# ZoomFloppy_v1_0.net
KiCad netlist of a schematic drawn in EAGLE
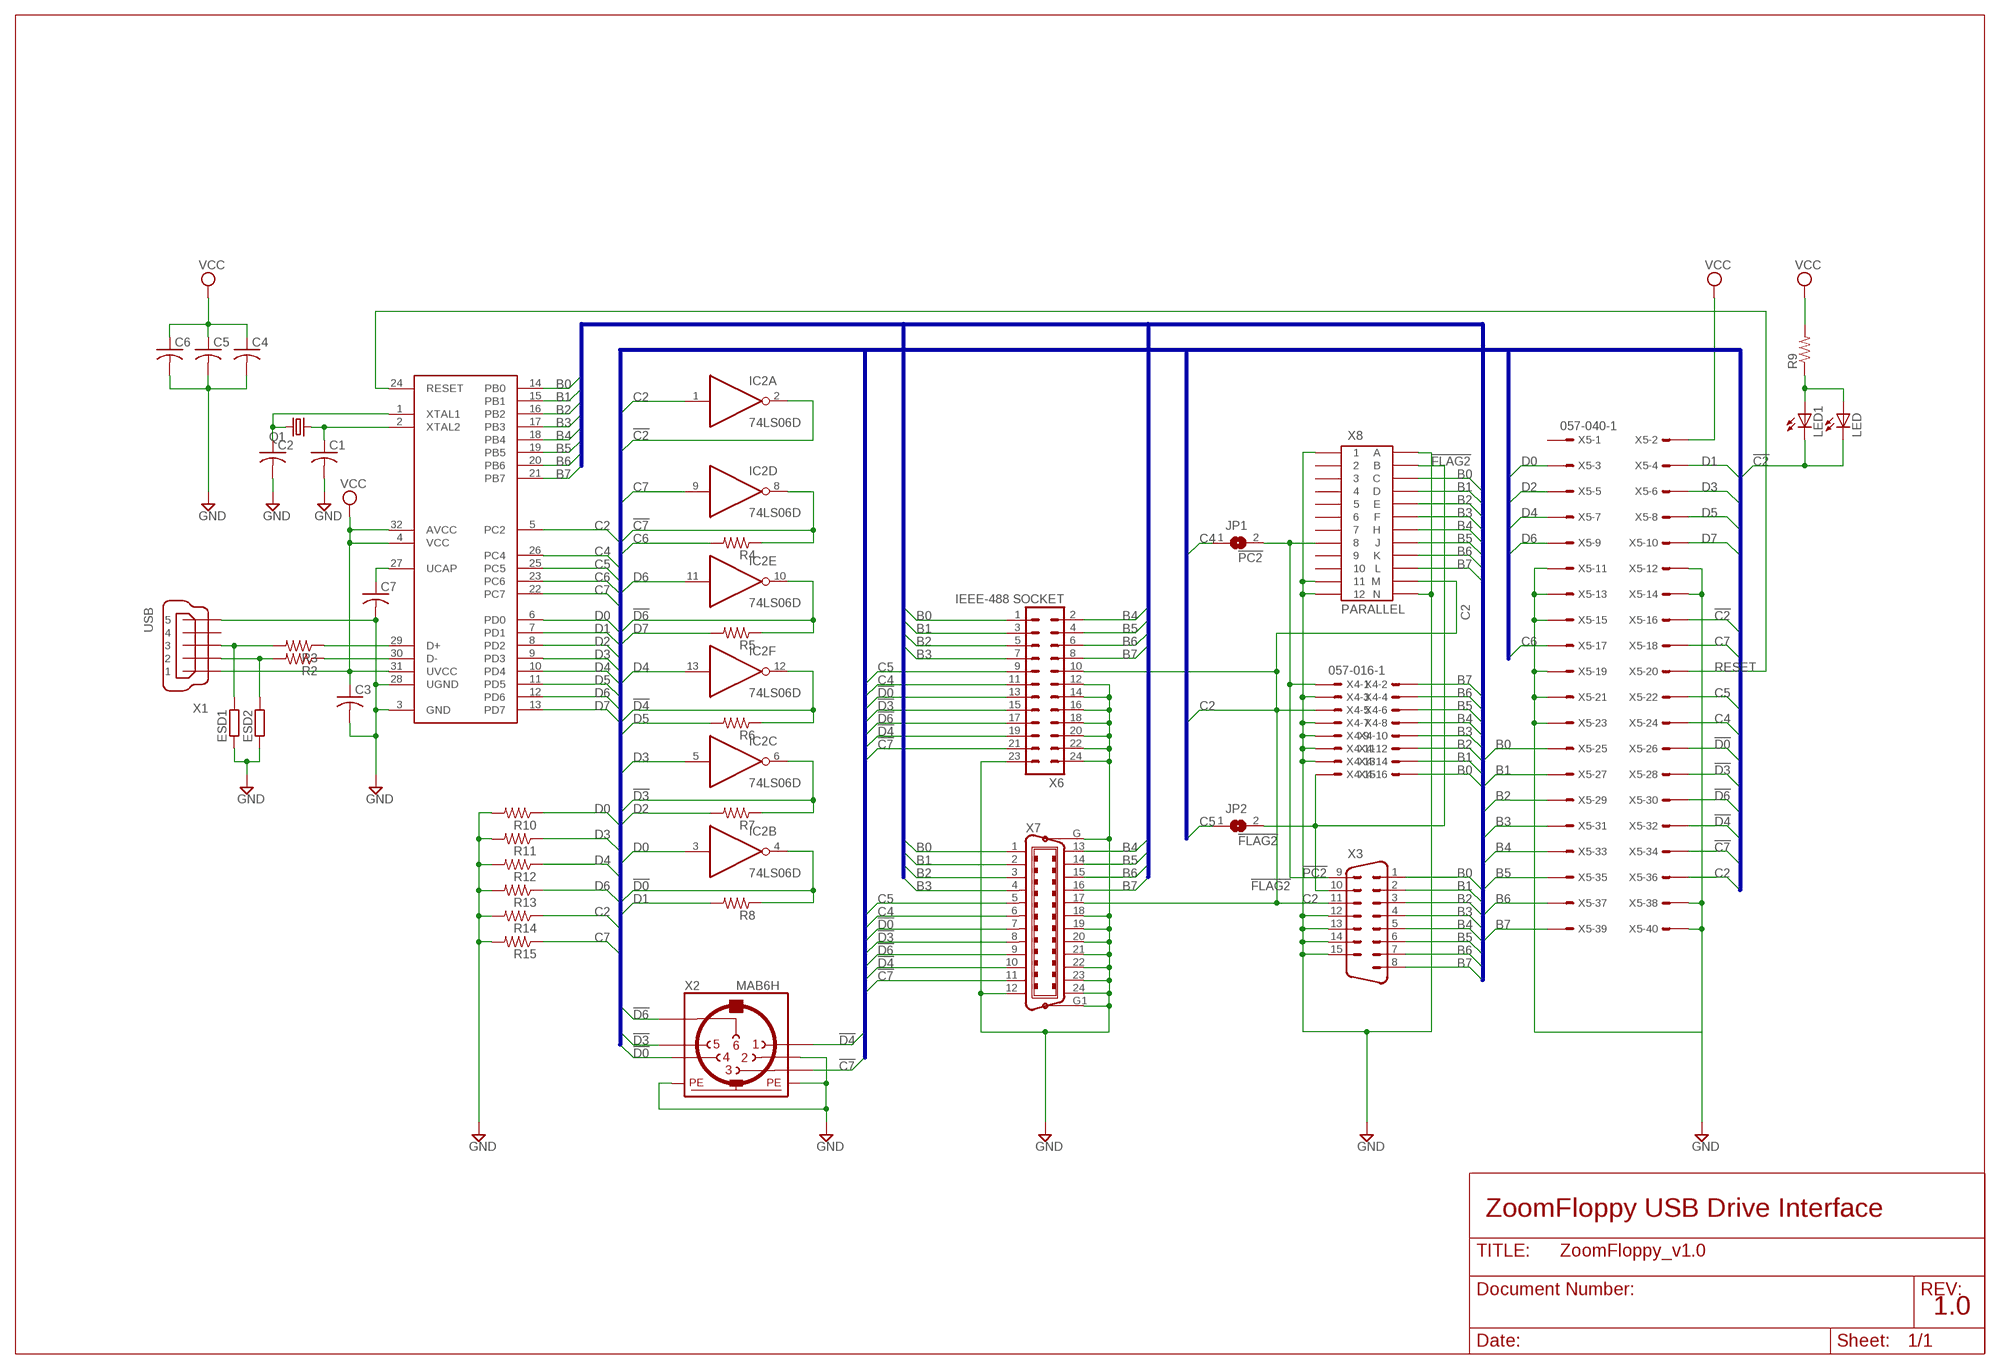
[diagram p0: schematic, sheet 1]

(export (version "E")
  (design (tool "Eeschema 10.0.6"))
  (components
    (comp (ref "C1")
      (value "C-USC0402")
      (footprint "eagle-import:C0402")
      (libsource (lib "eagle-import") (part "C-USC0402"))
    )
    (comp (ref "C2")
      (value "C-USC0402")
      (footprint "eagle-import:C0402")
      (libsource (lib "eagle-import") (part "C-USC0402"))
    )
    (comp (ref "C3")
      (value "C-USC0402")
      (footprint "eagle-import:C0402")
      (libsource (lib "eagle-import") (part "C-USC0402"))
    )
    (comp (ref "C4")
      (value "C-USC0402")
      (footprint "eagle-import:C0402")
      (libsource (lib "eagle-import") (part "C-USC0402"))
    )
    (comp (ref "C5")
      (value "C-USC0402")
      (footprint "eagle-import:C0402")
      (libsource (lib "eagle-import") (part "C-USC0402"))
    )
    (comp (ref "C6")
      (value "C-USC0402")
      (footprint "eagle-import:C0402")
      (libsource (lib "eagle-import") (part "C-USC0402"))
    )
    (comp (ref "C7")
      (value "C-USC0402")
      (footprint "eagle-import:C0402")
      (libsource (lib "eagle-import") (part "C-USC0402"))
    )
    (comp (ref "ESD1")
      (value "R-EU_R0603")
      (footprint "eagle-import:R0603")
      (libsource (lib "eagle-import") (part "R-EU_R0603"))
    )
    (comp (ref "ESD2")
      (value "R-EU_R0603")
      (footprint "eagle-import:R0603")
      (libsource (lib "eagle-import") (part "R-EU_R0603"))
    )
    (comp (ref "IC1")
      (value "ATMEGA32U2")
      (footprint "eagle-import:VQFP32")
      (libsource (lib "eagle-import") (part "AT90USB162"))
    )
    (comp (ref "IC2")
      (value "74LS06D")
      (footprint "eagle-import:SO14")
      (libsource (lib "eagle-import") (part "7406DLS"))
    )
    (comp (ref "JP1") (value "SJ") (footprint "eagle-import:SJ") (libsource (lib "eagle-import") (part "SJ")))
    (comp (ref "JP2") (value "SJ") (footprint "eagle-import:SJ") (libsource (lib "eagle-import") (part "SJ")))
    (comp (ref "LED")
      (value "LED3MM")
      (footprint "eagle-import:LED3MM")
      (libsource (lib "eagle-import") (part "LED3MM"))
    )
    (comp (ref "LED1")
      (value "LEDCHIP-LED0805")
      (footprint "eagle-import:CHIP-LED0805")
      (libsource (lib "eagle-import") (part "LEDCHIP-LED0805"))
    )
    (comp (ref "Q1")
      (value "CRYSTALHC49UP")
      (footprint "eagle-import:HC49UP")
      (libsource (lib "eagle-import") (part "CRYSTALHC49UP"))
    )
    (comp (ref "R2")
      (value "R-US_R0402")
      (footprint "eagle-import:R0402")
      (libsource (lib "eagle-import") (part "R-US_R0402"))
    )
    (comp (ref "R3")
      (value "R-US_R0402")
      (footprint "eagle-import:R0402")
      (libsource (lib "eagle-import") (part "R-US_R0402"))
    )
    (comp (ref "R4")
      (value "R-US_R0402")
      (footprint "eagle-import:R0402")
      (libsource (lib "eagle-import") (part "R-US_R0402"))
    )
    (comp (ref "R5")
      (value "R-US_R0402")
      (footprint "eagle-import:R0402")
      (libsource (lib "eagle-import") (part "R-US_R0402"))
    )
    (comp (ref "R6")
      (value "R-US_R0402")
      (footprint "eagle-import:R0402")
      (libsource (lib "eagle-import") (part "R-US_R0402"))
    )
    (comp (ref "R7")
      (value "R-US_R0402")
      (footprint "eagle-import:R0402")
      (libsource (lib "eagle-import") (part "R-US_R0402"))
    )
    (comp (ref "R8")
      (value "R-US_R0402")
      (footprint "eagle-import:R0402")
      (libsource (lib "eagle-import") (part "R-US_R0402"))
    )
    (comp (ref "R9")
      (value "R-US_R0402")
      (footprint "eagle-import:R0402")
      (libsource (lib "eagle-import") (part "R-US_R0402"))
    )
    (comp (ref "R10")
      (value "R-US_R0402")
      (footprint "eagle-import:R0402")
      (libsource (lib "eagle-import") (part "R-US_R0402"))
    )
    (comp (ref "R11")
      (value "R-US_R0402")
      (footprint "eagle-import:R0402")
      (libsource (lib "eagle-import") (part "R-US_R0402"))
    )
    (comp (ref "R12")
      (value "R-US_R0402")
      (footprint "eagle-import:R0402")
      (libsource (lib "eagle-import") (part "R-US_R0402"))
    )
    (comp (ref "R13")
      (value "R-US_R0402")
      (footprint "eagle-import:R0402")
      (libsource (lib "eagle-import") (part "R-US_R0402"))
    )
    (comp (ref "R14")
      (value "R-US_R0402")
      (footprint "eagle-import:R0402")
      (libsource (lib "eagle-import") (part "R-US_R0402"))
    )
    (comp (ref "R15")
      (value "R-US_R0402")
      (footprint "eagle-import:R0402")
      (libsource (lib "eagle-import") (part "R-US_R0402"))
    )
    (comp (ref "X1")
      (value "USB")
      (footprint "eagle-import:UX60-MB-5ST")
      (libsource (lib "eagle-import") (part "MINI-USB-UX60-MB-5ST"))
    )
    (comp (ref "X2")
      (value "MAB6H")
      (footprint "eagle-import:MAB6H")
      (libsource (lib "eagle-import") (part "MAB6H"))
    )
    (comp (ref "X3")
      (value "M15-182")
      (footprint "eagle-import:182-015-MALE")
      (libsource (lib "eagle-import") (part "M15-182"))
    )
    (comp (ref "X4")
      (value "057-016-1")
      (footprint "eagle-import:057-016-1")
      (libsource (lib "eagle-import") (part "057-016-1"))
    )
    (comp (ref "X5")
      (value "057-040-1")
      (footprint "eagle-import:057-040-1")
      (libsource (lib "eagle-import") (part "057-040-1"))
    )
    (comp (ref "X6")
      (value "IEEE-488 SOCKET")
      (footprint "eagle-import:MA12-2")
      (libsource (lib "eagle-import") (part "MA12-2"))
    )
    (comp (ref "X7")
      (value "C24HP")
      (footprint "eagle-import:24HP")
      (libsource (lib "eagle-import") (part "C24HP"))
    )
    (comp (ref "X8")
      (value "PARALLEL")
      (footprint "eagle-import:MA-24")
      (libsource (lib "eagle-import") (part "MA-24"))
    )
  )
  (nets
    (net (code "1") (name "/B0") (class "Default")
      (node (ref "IC1") (pin "14") (pinfunction "PB0_14") (pintype "bidirectional"))
      (node (ref "X3") (pin "1") (pinfunction "1_1") (pintype "passive"))
      (node (ref "X4") (pin "16") (pinfunction "S_16") (pintype "passive"))
      (node (ref "X5") (pin "25") (pinfunction "S_25") (pintype "passive"))
      (node (ref "X6") (pin "1") (pinfunction "1_1") (pintype "passive"))
      (node (ref "X7") (pin "1") (pinfunction "1_1") (pintype "passive"))
      (node (ref "X8") (pin "C") (pinfunction "C_C") (pintype "passive"))
    )
    (net (code "2") (name "/B1") (class "Default")
      (node (ref "IC1") (pin "15") (pinfunction "PB1_15") (pintype "bidirectional"))
      (node (ref "X3") (pin "2") (pinfunction "2_2") (pintype "passive"))
      (node (ref "X4") (pin "14") (pinfunction "S_14") (pintype "passive"))
      (node (ref "X5") (pin "27") (pinfunction "S_27") (pintype "passive"))
      (node (ref "X6") (pin "3") (pinfunction "3_3") (pintype "passive"))
      (node (ref "X7") (pin "2") (pinfunction "2_2") (pintype "passive"))
      (node (ref "X8") (pin "D") (pinfunction "D_D") (pintype "passive"))
    )
    (net (code "3") (name "/B2") (class "Default")
      (node (ref "IC1") (pin "16") (pinfunction "PB2_16") (pintype "bidirectional"))
      (node (ref "X3") (pin "3") (pinfunction "3_3") (pintype "passive"))
      (node (ref "X4") (pin "12") (pinfunction "S_12") (pintype "passive"))
      (node (ref "X5") (pin "29") (pinfunction "S_29") (pintype "passive"))
      (node (ref "X6") (pin "5") (pinfunction "5_5") (pintype "passive"))
      (node (ref "X7") (pin "3") (pinfunction "3_3") (pintype "passive"))
      (node (ref "X8") (pin "E") (pinfunction "E_E") (pintype "passive"))
    )
    (net (code "4") (name "/B3") (class "Default")
      (node (ref "IC1") (pin "17") (pinfunction "PB3_17") (pintype "bidirectional"))
      (node (ref "X3") (pin "4") (pinfunction "4_4") (pintype "passive"))
      (node (ref "X4") (pin "10") (pinfunction "S_10") (pintype "passive"))
      (node (ref "X5") (pin "31") (pinfunction "S_31") (pintype "passive"))
      (node (ref "X6") (pin "7") (pinfunction "7_7") (pintype "passive"))
      (node (ref "X7") (pin "4") (pinfunction "4_4") (pintype "passive"))
      (node (ref "X8") (pin "F") (pinfunction "F_F") (pintype "passive"))
    )
    (net (code "5") (name "/B4") (class "Default")
      (node (ref "IC1") (pin "18") (pinfunction "PB4_18") (pintype "bidirectional"))
      (node (ref "X3") (pin "5") (pinfunction "5_5") (pintype "passive"))
      (node (ref "X4") (pin "8") (pinfunction "S_8") (pintype "passive"))
      (node (ref "X5") (pin "33") (pinfunction "S_33") (pintype "passive"))
      (node (ref "X6") (pin "2") (pinfunction "2_2") (pintype "passive"))
      (node (ref "X7") (pin "13") (pinfunction "13_13") (pintype "passive"))
      (node (ref "X8") (pin "H") (pinfunction "H_H") (pintype "passive"))
    )
    (net (code "6") (name "/B5") (class "Default")
      (node (ref "IC1") (pin "19") (pinfunction "PB5_19") (pintype "bidirectional"))
      (node (ref "X3") (pin "6") (pinfunction "6_6") (pintype "passive"))
      (node (ref "X4") (pin "6") (pinfunction "S_6") (pintype "passive"))
      (node (ref "X5") (pin "35") (pinfunction "S_35") (pintype "passive"))
      (node (ref "X6") (pin "4") (pinfunction "4_4") (pintype "passive"))
      (node (ref "X7") (pin "14") (pinfunction "14_14") (pintype "passive"))
      (node (ref "X8") (pin "J") (pinfunction "J_J") (pintype "passive"))
    )
    (net (code "7") (name "/B6") (class "Default")
      (node (ref "IC1") (pin "20") (pinfunction "PB6_20") (pintype "bidirectional"))
      (node (ref "X3") (pin "7") (pinfunction "7_7") (pintype "passive"))
      (node (ref "X4") (pin "4") (pinfunction "S_4") (pintype "passive"))
      (node (ref "X5") (pin "37") (pinfunction "S_37") (pintype "passive"))
      (node (ref "X6") (pin "6") (pinfunction "6_6") (pintype "passive"))
      (node (ref "X7") (pin "15") (pinfunction "15_15") (pintype "passive"))
      (node (ref "X8") (pin "K") (pinfunction "K_K") (pintype "passive"))
    )
    (net (code "8") (name "/B7") (class "Default")
      (node (ref "IC1") (pin "21") (pinfunction "PB7_21") (pintype "bidirectional"))
      (node (ref "X3") (pin "8") (pinfunction "8_8") (pintype "passive"))
      (node (ref "X4") (pin "2") (pinfunction "S_2") (pintype "passive"))
      (node (ref "X5") (pin "39") (pinfunction "S_39") (pintype "passive"))
      (node (ref "X6") (pin "8") (pinfunction "8_8") (pintype "passive"))
      (node (ref "X7") (pin "16") (pinfunction "16_16") (pintype "passive"))
      (node (ref "X8") (pin "L") (pinfunction "L_L") (pintype "passive"))
    )
    (net (code "9") (name "/C2") (class "Default")
      (node (ref "IC1") (pin "5") (pinfunction "PC2_5") (pintype "bidirectional"))
      (node (ref "IC2") (pin "1") (pinfunction "I_1") (pintype "input"))
      (node (ref "R14") (pin "1") (pinfunction "1_1") (pintype "passive"))
      (node (ref "X3") (pin "11") (pinfunction "11_11") (pintype "passive"))
      (node (ref "X4") (pin "5") (pinfunction "S_5") (pintype "passive"))
      (node (ref "X5") (pin "36") (pinfunction "S_36") (pintype "passive"))
      (node (ref "X6") (pin "10") (pinfunction "10_10") (pintype "passive"))
      (node (ref "X7") (pin "17") (pinfunction "17_17") (pintype "passive"))
      (node (ref "X8") (pin "M") (pinfunction "M_M") (pintype "passive"))
    )
    (net (code "10") (name "/C4") (class "Default")
      (node (ref "IC1") (pin "26") (pinfunction "PC4_26") (pintype "bidirectional"))
      (node (ref "JP1") (pin "1") (pinfunction "1_1") (pintype "passive"))
      (node (ref "X5") (pin "24") (pinfunction "S_24") (pintype "passive"))
      (node (ref "X6") (pin "11") (pinfunction "11_11") (pintype "passive"))
      (node (ref "X7") (pin "6") (pinfunction "6_6") (pintype "passive"))
    )
    (net (code "11") (name "/C5") (class "Default")
      (node (ref "IC1") (pin "25") (pinfunction "PC5_25") (pintype "bidirectional"))
      (node (ref "JP2") (pin "1") (pinfunction "1_1") (pintype "passive"))
      (node (ref "X5") (pin "22") (pinfunction "S_22") (pintype "passive"))
      (node (ref "X6") (pin "9") (pinfunction "9_9") (pintype "passive"))
      (node (ref "X7") (pin "5") (pinfunction "5_5") (pintype "passive"))
    )
    (net (code "12") (name "/C6") (class "Default")
      (node (ref "IC1") (pin "23") (pinfunction "PC6_23") (pintype "bidirectional"))
      (node (ref "R4") (pin "2") (pinfunction "2_2") (pintype "passive"))
      (node (ref "X5") (pin "17") (pinfunction "S_17") (pintype "passive"))
    )
    (net (code "13") (name "/C7") (class "Default")
      (node (ref "IC1") (pin "22") (pinfunction "PC7_22") (pintype "bidirectional"))
      (node (ref "IC2") (pin "9") (pinfunction "I_9") (pintype "input"))
      (node (ref "R15") (pin "1") (pinfunction "1_1") (pintype "passive"))
      (node (ref "X5") (pin "18") (pinfunction "S_18") (pintype "passive"))
    )
    (net (code "14") (name "/D0") (class "Default")
      (node (ref "IC1") (pin "6") (pinfunction "PD0_6") (pintype "bidirectional"))
      (node (ref "IC2") (pin "3") (pinfunction "I_3") (pintype "input"))
      (node (ref "R10") (pin "1") (pinfunction "1_1") (pintype "passive"))
      (node (ref "X5") (pin "3") (pinfunction "S_3") (pintype "passive"))
    )
    (net (code "15") (name "/D1") (class "Default")
      (node (ref "IC1") (pin "7") (pinfunction "PD1_7") (pintype "bidirectional"))
      (node (ref "R8") (pin "2") (pinfunction "2_2") (pintype "passive"))
      (node (ref "X5") (pin "4") (pinfunction "S_4") (pintype "passive"))
    )
    (net (code "16") (name "/D2") (class "Default")
      (node (ref "IC1") (pin "8") (pinfunction "PD2_8") (pintype "bidirectional"))
      (node (ref "R7") (pin "2") (pinfunction "2_2") (pintype "passive"))
      (node (ref "X5") (pin "5") (pinfunction "S_5") (pintype "passive"))
    )
    (net (code "17") (name "/D3") (class "Default")
      (node (ref "IC1") (pin "9") (pinfunction "PD3_9") (pintype "bidirectional"))
      (node (ref "IC2") (pin "5") (pinfunction "I_5") (pintype "input"))
      (node (ref "R11") (pin "1") (pinfunction "1_1") (pintype "passive"))
      (node (ref "X5") (pin "6") (pinfunction "S_6") (pintype "passive"))
    )
    (net (code "18") (name "/D4") (class "Default")
      (node (ref "IC1") (pin "10") (pinfunction "PD4_10") (pintype "bidirectional"))
      (node (ref "IC2") (pin "13") (pinfunction "I_13") (pintype "input"))
      (node (ref "R12") (pin "1") (pinfunction "1_1") (pintype "passive"))
      (node (ref "X5") (pin "7") (pinfunction "S_7") (pintype "passive"))
    )
    (net (code "19") (name "/D5") (class "Default")
      (node (ref "IC1") (pin "11") (pinfunction "PD5_11") (pintype "bidirectional"))
      (node (ref "R6") (pin "2") (pinfunction "2_2") (pintype "passive"))
      (node (ref "X5") (pin "8") (pinfunction "S_8") (pintype "passive"))
    )
    (net (code "20") (name "/D6") (class "Default")
      (node (ref "IC1") (pin "12") (pinfunction "PD6_12") (pintype "bidirectional"))
      (node (ref "IC2") (pin "11") (pinfunction "I_11") (pintype "input"))
      (node (ref "R13") (pin "1") (pinfunction "1_1") (pintype "passive"))
      (node (ref "X5") (pin "9") (pinfunction "S_9") (pintype "passive"))
    )
    (net (code "21") (name "/D7") (class "Default")
      (node (ref "IC1") (pin "13") (pinfunction "PD7_13") (pintype "bidirectional"))
      (node (ref "R5") (pin "2") (pinfunction "2_2") (pintype "passive"))
      (node (ref "X5") (pin "10") (pinfunction "S_10") (pintype "passive"))
    )
    (net (code "22") (name "/RESET") (class "Default")
      (node (ref "IC1") (pin "24") (pinfunction "RESET_24") (pintype "bidirectional"))
      (node (ref "X5") (pin "20") (pinfunction "S_20") (pintype "passive"))
    )
    (net (code "23") (name "/~{C2}") (class "Default")
      (node (ref "IC2") (pin "2") (pinfunction "O_2") (pintype "open_collector"))
      (node (ref "LED") (pin "K") (pinfunction "C_K") (pintype "passive"))
      (node (ref "LED1") (pin "C") (pinfunction "C_C") (pintype "passive"))
      (node (ref "X5") (pin "16") (pinfunction "S_16") (pintype "passive"))
    )
    (net (code "24") (name "/~{C7}") (class "Default")
      (node (ref "IC2") (pin "8") (pinfunction "O_8") (pintype "open_collector"))
      (node (ref "R4") (pin "1") (pinfunction "1_1") (pintype "passive"))
      (node (ref "X2") (pin "3") (pinfunction "3_3") (pintype "passive"))
      (node (ref "X5") (pin "34") (pinfunction "S_34") (pintype "passive"))
      (node (ref "X6") (pin "21") (pinfunction "21_21") (pintype "passive"))
      (node (ref "X7") (pin "11") (pinfunction "11_11") (pintype "passive"))
    )
    (net (code "25") (name "/~{D0}") (class "Default")
      (node (ref "IC2") (pin "4") (pinfunction "O_4") (pintype "open_collector"))
      (node (ref "R8") (pin "1") (pinfunction "1_1") (pintype "passive"))
      (node (ref "X2") (pin "4") (pinfunction "4_4") (pintype "passive"))
      (node (ref "X5") (pin "26") (pinfunction "S_26") (pintype "passive"))
      (node (ref "X6") (pin "13") (pinfunction "13_13") (pintype "passive"))
      (node (ref "X7") (pin "7") (pinfunction "7_7") (pintype "passive"))
    )
    (net (code "26") (name "/~{D3}") (class "Default")
      (node (ref "IC2") (pin "6") (pinfunction "O_6") (pintype "open_collector"))
      (node (ref "R7") (pin "1") (pinfunction "1_1") (pintype "passive"))
      (node (ref "X2") (pin "5") (pinfunction "5_5") (pintype "passive"))
      (node (ref "X5") (pin "28") (pinfunction "S_28") (pintype "passive"))
      (node (ref "X6") (pin "15") (pinfunction "15_15") (pintype "passive"))
      (node (ref "X7") (pin "8") (pinfunction "8_8") (pintype "passive"))
    )
    (net (code "27") (name "/~{D4}") (class "Default")
      (node (ref "IC2") (pin "12") (pinfunction "O_12") (pintype "open_collector"))
      (node (ref "R6") (pin "1") (pinfunction "1_1") (pintype "passive"))
      (node (ref "X2") (pin "1") (pinfunction "1_1") (pintype "passive"))
      (node (ref "X5") (pin "32") (pinfunction "S_32") (pintype "passive"))
      (node (ref "X6") (pin "19") (pinfunction "19_19") (pintype "passive"))
      (node (ref "X7") (pin "10") (pinfunction "10_10") (pintype "passive"))
    )
    (net (code "28") (name "/~{D6}") (class "Default")
      (node (ref "IC2") (pin "10") (pinfunction "O_10") (pintype "open_collector"))
      (node (ref "R5") (pin "1") (pinfunction "1_1") (pintype "passive"))
      (node (ref "X2") (pin "6") (pinfunction "6_6") (pintype "passive"))
      (node (ref "X5") (pin "30") (pinfunction "S_30") (pintype "passive"))
      (node (ref "X6") (pin "17") (pinfunction "17_17") (pintype "passive"))
      (node (ref "X7") (pin "9") (pinfunction "9_9") (pintype "passive"))
    )
    (net (code "29") (name "/~{FLAG2}") (class "Default")
      (node (ref "JP2") (pin "2") (pinfunction "2_2") (pintype "passive"))
      (node (ref "X3") (pin "10") (pinfunction "10_10") (pintype "passive"))
      (node (ref "X4") (pin "15") (pinfunction "S_15") (pintype "passive"))
      (node (ref "X8") (pin "B") (pinfunction "B_B") (pintype "passive"))
    )
    (net (code "30") (name "/~{PC2}") (class "Default")
      (node (ref "JP1") (pin "2") (pinfunction "2_2") (pintype "passive"))
      (node (ref "X3") (pin "9") (pinfunction "9_9") (pintype "passive"))
      (node (ref "X4") (pin "1") (pinfunction "S_1") (pintype "passive"))
      (node (ref "X8") (pin "8") (pinfunction "8_8") (pintype "passive"))
    )
    (net (code "31") (name "GND") (class "Default")
      (node (ref "C1") (pin "2") (pinfunction "2_2") (pintype "passive"))
      (node (ref "C2") (pin "2") (pinfunction "2_2") (pintype "passive"))
      (node (ref "C3") (pin "2") (pinfunction "2_2") (pintype "passive"))
      (node (ref "C4") (pin "2") (pinfunction "2_2") (pintype "passive"))
      (node (ref "C5") (pin "2") (pinfunction "2_2") (pintype "passive"))
      (node (ref "C6") (pin "2") (pinfunction "2_2") (pintype "passive"))
      (node (ref "C7") (pin "2") (pinfunction "2_2") (pintype "passive"))
      (node (ref "ESD1") (pin "1") (pinfunction "1_1") (pintype "passive"))
      (node (ref "ESD2") (pin "1") (pinfunction "1_1") (pintype "passive"))
      (node (ref "IC1") (pin "28") (pinfunction "UGND_28") (pintype "bidirectional"))
      (node (ref "IC1") (pin "3") (pinfunction "GND_3") (pintype "power_in"))
      (node (ref "R10") (pin "2") (pinfunction "2_2") (pintype "passive"))
      (node (ref "R11") (pin "2") (pinfunction "2_2") (pintype "passive"))
      (node (ref "R12") (pin "2") (pinfunction "2_2") (pintype "passive"))
      (node (ref "R13") (pin "2") (pinfunction "2_2") (pintype "passive"))
      (node (ref "R14") (pin "2") (pinfunction "2_2") (pintype "passive"))
      (node (ref "R15") (pin "2") (pinfunction "2_2") (pintype "passive"))
      (node (ref "X1") (pin "5") (pinfunction "5_5") (pintype "input"))
      (node (ref "X2") (pin "2") (pinfunction "2_2") (pintype "passive"))
      (node (ref "X2") (pin "PE") (pinfunction "PE_PE") (pintype "power_in"))
      (node (ref "X2") (pin "PE@") (pinfunction "PE_PE@") (pintype "power_in"))
      (node (ref "X3") (pin "12") (pinfunction "12_12") (pintype "passive"))
      (node (ref "X3") (pin "13") (pinfunction "13_13") (pintype "passive"))
      (node (ref "X3") (pin "14") (pinfunction "14_14") (pintype "passive"))
      (node (ref "X3") (pin "15") (pinfunction "15_15") (pintype "passive"))
      (node (ref "X4") (pin "11") (pinfunction "S_11") (pintype "passive"))
      (node (ref "X4") (pin "13") (pinfunction "S_13") (pintype "passive"))
      (node (ref "X4") (pin "3") (pinfunction "S_3") (pintype "passive"))
      (node (ref "X4") (pin "7") (pinfunction "S_7") (pintype "passive"))
      (node (ref "X4") (pin "9") (pinfunction "S_9") (pintype "passive"))
      (node (ref "X5") (pin "11") (pinfunction "S_11") (pintype "passive"))
      (node (ref "X5") (pin "12") (pinfunction "S_12") (pintype "passive"))
      (node (ref "X5") (pin "13") (pinfunction "S_13") (pintype "passive"))
      (node (ref "X5") (pin "14") (pinfunction "S_14") (pintype "passive"))
      (node (ref "X5") (pin "15") (pinfunction "S_15") (pintype "passive"))
      (node (ref "X5") (pin "19") (pinfunction "S_19") (pintype "passive"))
      (node (ref "X5") (pin "21") (pinfunction "S_21") (pintype "passive"))
      (node (ref "X5") (pin "23") (pinfunction "S_23") (pintype "passive"))
      (node (ref "X5") (pin "38") (pinfunction "S_38") (pintype "passive"))
      (node (ref "X5") (pin "40") (pinfunction "S_40") (pintype "passive"))
      (node (ref "X6") (pin "12") (pinfunction "12_12") (pintype "passive"))
      (node (ref "X6") (pin "14") (pinfunction "14_14") (pintype "passive"))
      (node (ref "X6") (pin "16") (pinfunction "16_16") (pintype "passive"))
      (node (ref "X6") (pin "18") (pinfunction "18_18") (pintype "passive"))
      (node (ref "X6") (pin "20") (pinfunction "20_20") (pintype "passive"))
      (node (ref "X6") (pin "22") (pinfunction "22_22") (pintype "passive"))
      (node (ref "X6") (pin "23") (pinfunction "23_23") (pintype "passive"))
      (node (ref "X6") (pin "24") (pinfunction "24_24") (pintype "passive"))
      (node (ref "X7") (pin "12") (pinfunction "12_12") (pintype "passive"))
      (node (ref "X7") (pin "18") (pinfunction "18_18") (pintype "passive"))
      (node (ref "X7") (pin "19") (pinfunction "19_19") (pintype "passive"))
      (node (ref "X7") (pin "20") (pinfunction "20_20") (pintype "passive"))
      (node (ref "X7") (pin "21") (pinfunction "21_21") (pintype "passive"))
      (node (ref "X7") (pin "22") (pinfunction "22_22") (pintype "passive"))
      (node (ref "X7") (pin "23") (pinfunction "23_23") (pintype "passive"))
      (node (ref "X7") (pin "24") (pinfunction "24_24") (pintype "passive"))
      (node (ref "X7") (pin "G") (pinfunction "G_G") (pintype "passive"))
      (node (ref "X7") (pin "G1") (pinfunction "G1_G1") (pintype "passive"))
      (node (ref "X8") (pin "1") (pinfunction "1_1") (pintype "passive"))
      (node (ref "X8") (pin "11") (pinfunction "11_11") (pintype "passive"))
      (node (ref "X8") (pin "12") (pinfunction "12_12") (pintype "passive"))
      (node (ref "X8") (pin "A") (pinfunction "A_A") (pintype "passive"))
      (node (ref "X8") (pin "N") (pinfunction "N_N") (pintype "passive"))
    )
    (net (code "32") (name "Net-(ESD1-Pad2)") (class "Default")
      (node (ref "ESD1") (pin "2") (pinfunction "2_2") (pintype "passive"))
      (node (ref "R3") (pin "2") (pinfunction "2_2") (pintype "passive"))
      (node (ref "X1") (pin "3") (pinfunction "3_3") (pintype "input"))
    )
    (net (code "33") (name "Net-(ESD2-Pad2)") (class "Default")
      (node (ref "ESD2") (pin "2") (pinfunction "2_2") (pintype "passive"))
      (node (ref "R2") (pin "2") (pinfunction "2_2") (pintype "passive"))
      (node (ref "X1") (pin "2") (pinfunction "2_2") (pintype "input"))
    )
    (net (code "34") (name "Net-(IC1-D+)") (class "Default")
      (node (ref "IC1") (pin "29") (pinfunction "D+_29") (pintype "bidirectional"))
      (node (ref "R3") (pin "1") (pinfunction "1_1") (pintype "passive"))
    )
    (net (code "35") (name "Net-(IC1-D-)") (class "Default")
      (node (ref "IC1") (pin "30") (pinfunction "D-_30") (pintype "bidirectional"))
      (node (ref "R2") (pin "1") (pinfunction "1_1") (pintype "passive"))
    )
    (net (code "36") (name "Net-(IC1-UCAP)") (class "Default")
      (node (ref "C7") (pin "1") (pinfunction "1_1") (pintype "passive"))
      (node (ref "IC1") (pin "27") (pinfunction "UCAP_27") (pintype "bidirectional"))
    )
    (net (code "37") (name "Net-(IC1-XTAL1)") (class "Default")
      (node (ref "C2") (pin "1") (pinfunction "1_1") (pintype "passive"))
      (node (ref "IC1") (pin "1") (pinfunction "XTAL1_1") (pintype "bidirectional"))
      (node (ref "Q1") (pin "2") (pinfunction "2_2") (pintype "passive"))
    )
    (net (code "38") (name "Net-(IC1-XTAL2)") (class "Default")
      (node (ref "C1") (pin "1") (pinfunction "1_1") (pintype "passive"))
      (node (ref "IC1") (pin "2") (pinfunction "XTAL2_2") (pintype "bidirectional"))
      (node (ref "Q1") (pin "1") (pinfunction "1_1") (pintype "passive"))
    )
    (net (code "39") (name "Net-(LED-PadA)") (class "Default")
      (node (ref "LED") (pin "A") (pinfunction "A_A") (pintype "passive"))
      (node (ref "LED1") (pin "A") (pinfunction "A_A") (pintype "passive"))
      (node (ref "R9") (pin "1") (pinfunction "1_1") (pintype "passive"))
    )
    (net (code "40") (name "VCC") (class "Default")
      (node (ref "C3") (pin "1") (pinfunction "1_1") (pintype "passive"))
      (node (ref "C4") (pin "1") (pinfunction "1_1") (pintype "passive"))
      (node (ref "C5") (pin "1") (pinfunction "1_1") (pintype "passive"))
      (node (ref "C6") (pin "1") (pinfunction "1_1") (pintype "passive"))
      (node (ref "IC1") (pin "31") (pinfunction "UVCC_31") (pintype "bidirectional"))
      (node (ref "IC1") (pin "32") (pinfunction "AVCC_32") (pintype "bidirectional"))
      (node (ref "IC1") (pin "4") (pinfunction "VCC_4") (pintype "power_in"))
      (node (ref "R9") (pin "2") (pinfunction "2_2") (pintype "passive"))
      (node (ref "X1") (pin "1") (pinfunction "1_1") (pintype "input"))
      (node (ref "X5") (pin "2") (pinfunction "S_2") (pintype "passive"))
    )
    (net (code "41") (name "unconnected-(X1-Pad4)") (class "Default")
      (node (ref "X1") (pin "4") (pinfunction "4_4") (pintype "input"))
    )
    (net (code "42") (name "unconnected-(X5A-S-Pad1)") (class "Default")
      (node (ref "X5") (pin "1") (pinfunction "S_1") (pintype "passive"))
    )
    (net (code "43") (name "unconnected-(X8-Pad2)") (class "Default")
      (node (ref "X8") (pin "2") (pinfunction "2_2") (pintype "passive"))
    )
    (net (code "44") (name "unconnected-(X8-Pad3)") (class "Default")
      (node (ref "X8") (pin "3") (pinfunction "3_3") (pintype "passive"))
    )
    (net (code "45") (name "unconnected-(X8-Pad4)") (class "Default")
      (node (ref "X8") (pin "4") (pinfunction "4_4") (pintype "passive"))
    )
    (net (code "46") (name "unconnected-(X8-Pad5)") (class "Default")
      (node (ref "X8") (pin "5") (pinfunction "5_5") (pintype "passive"))
    )
    (net (code "47") (name "unconnected-(X8-Pad6)") (class "Default")
      (node (ref "X8") (pin "6") (pinfunction "6_6") (pintype "passive"))
    )
    (net (code "48") (name "unconnected-(X8-Pad7)") (class "Default")
      (node (ref "X8") (pin "7") (pinfunction "7_7") (pintype "passive"))
    )
    (net (code "49") (name "unconnected-(X8-Pad9)") (class "Default")
      (node (ref "X8") (pin "9") (pinfunction "9_9") (pintype "passive"))
    )
    (net (code "50") (name "unconnected-(X8-Pad10)") (class "Default")
      (node (ref "X8") (pin "10") (pinfunction "10_10") (pintype "passive"))
    )
  )
)
